# 140716_AriloTX_REV3_0_0_868MHZ_td.net
KiCad netlist of a schematic drawn in EAGLE
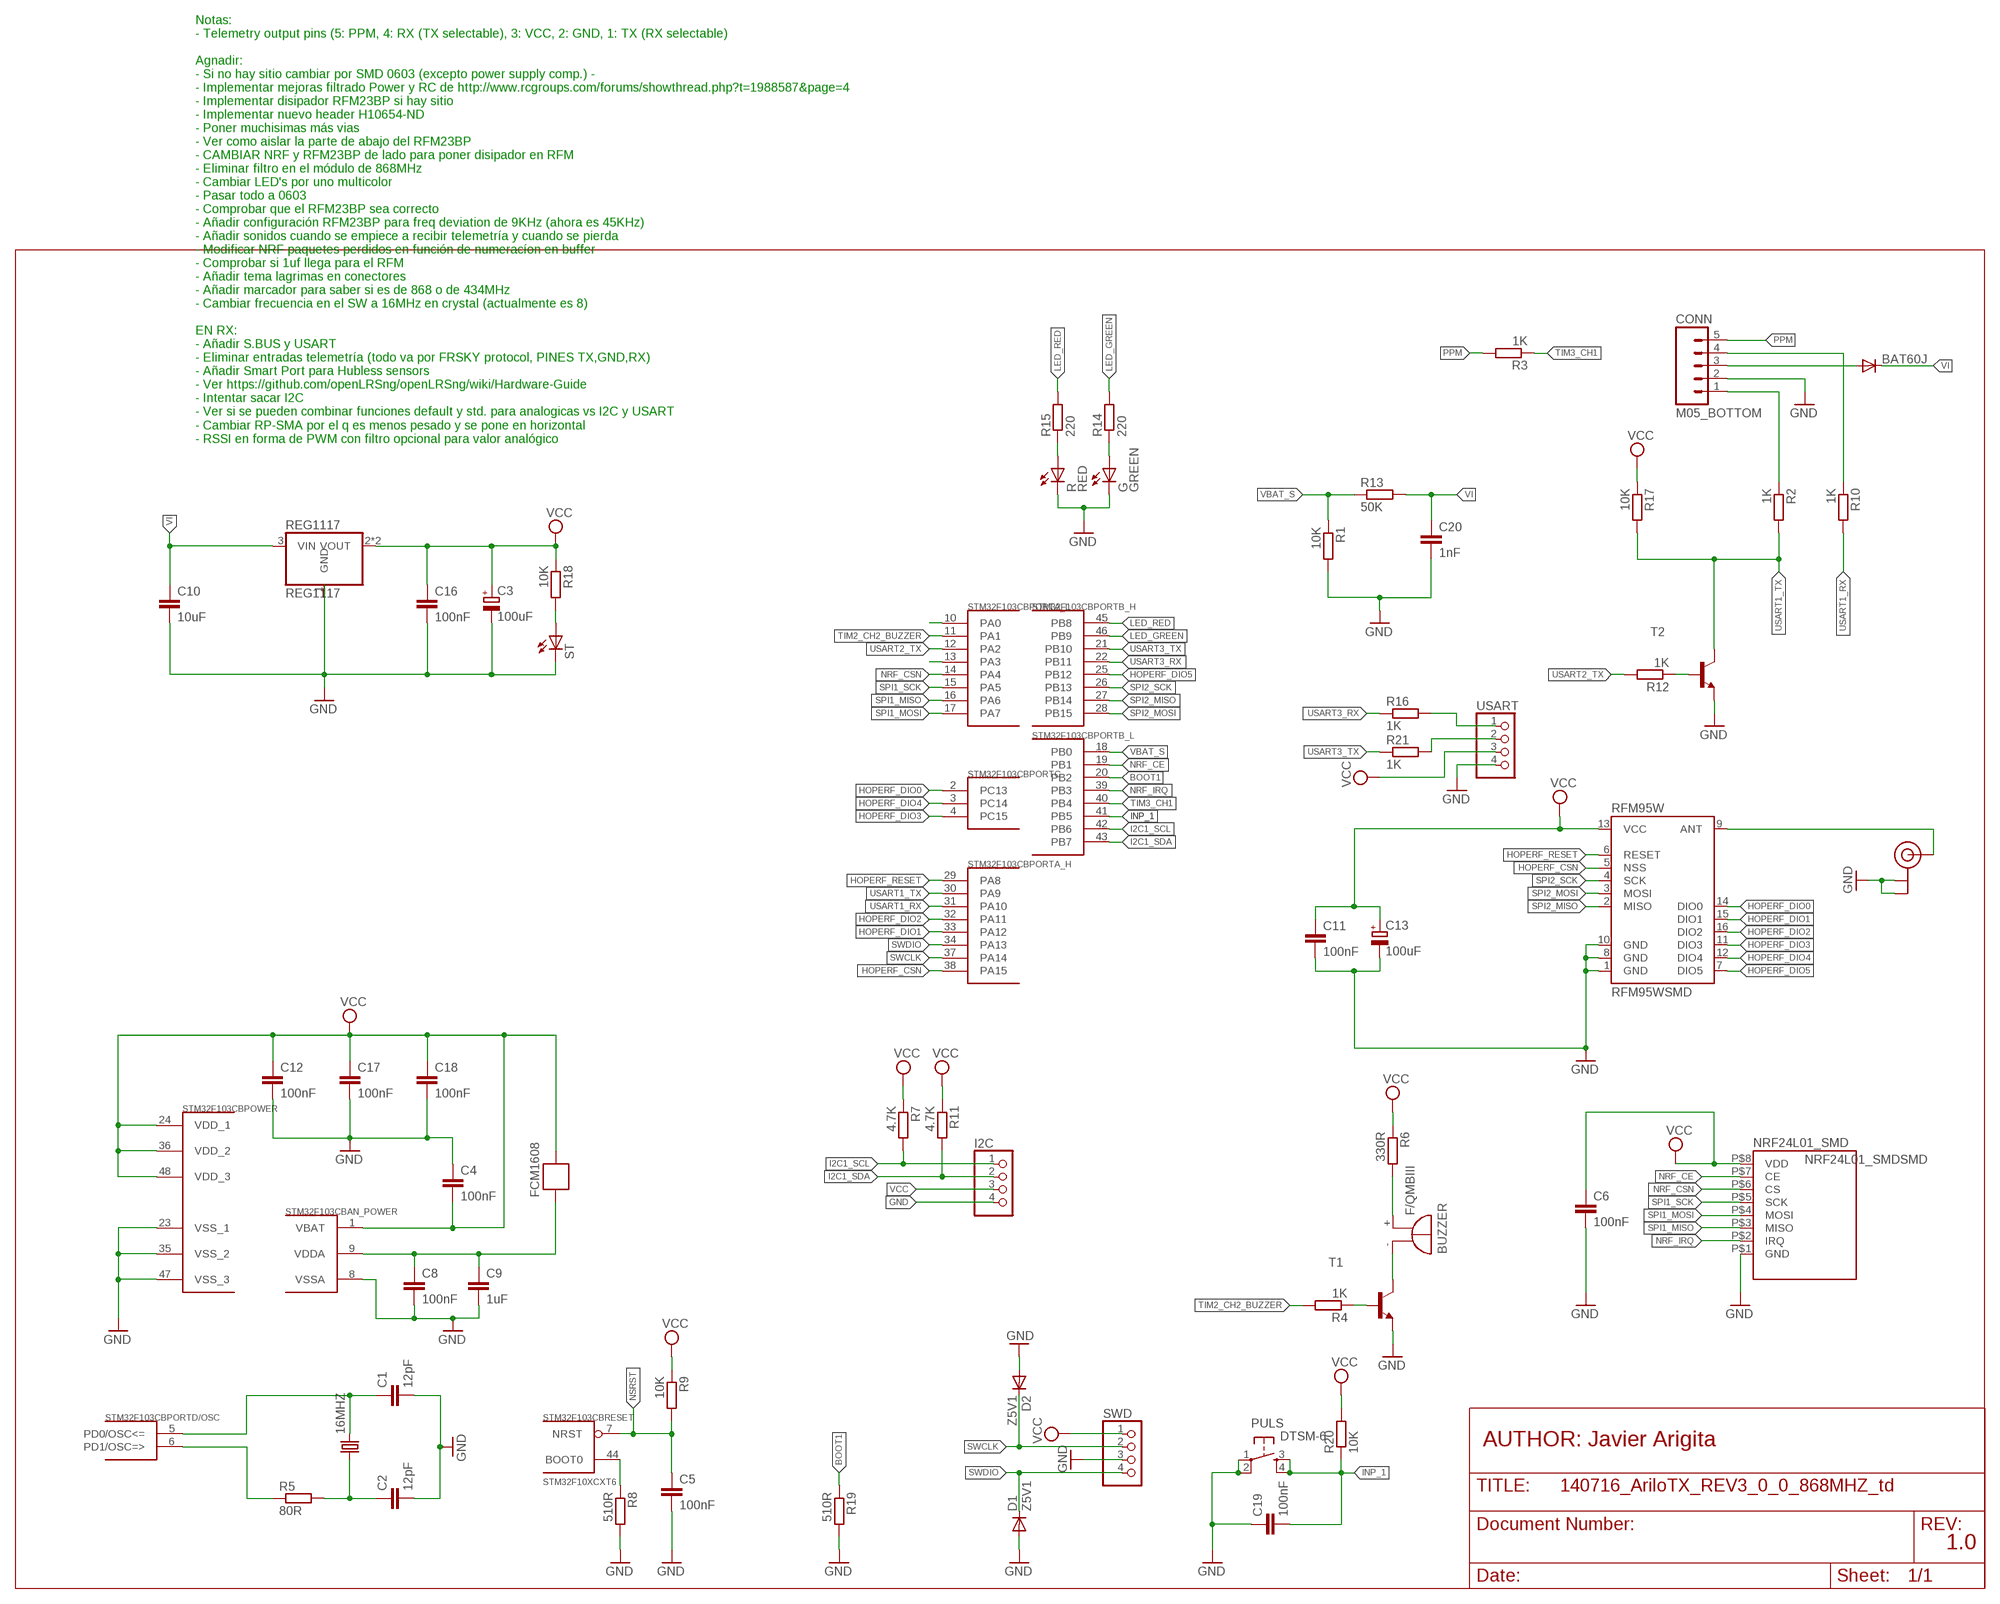
[diagram p0: schematic, sheet 1]

(export (version "E")
  (design (tool "Eeschema 10.0.6"))
  (components
    (comp (ref "16MHZ")
      (value "CRYSTAL5X3")
      (footprint "eagle-import:CRYSTAL-SMD-5X3")
      (libsource (lib "eagle-import") (part "CRYSTAL5X3"))
    )
    (comp (ref "BAT60J")
      (value "DIODE-SOD323-R")
      (footprint "eagle-import:SOD323-R")
      (libsource (lib "eagle-import") (part "DIODE-SOD323-R"))
    )
    (comp (ref "BUZZER")
      (value "F/QMBIII")
      (footprint "eagle-import:F_QMBIII")
      (libsource (lib "eagle-import") (part "F/QMBIII"))
    )
    (comp (ref "C1")
      (value "12pF")
      (footprint "eagle-import:C0603")
      (libsource (lib "eagle-import") (part "C-EUC0603"))
    )
    (comp (ref "C2")
      (value "12pF")
      (footprint "eagle-import:C0603")
      (libsource (lib "eagle-import") (part "C-EUC0603"))
    )
    (comp (ref "C3")
      (value "100uF")
      (footprint "eagle-import:SMC_B")
      (libsource (lib "eagle-import") (part "CPOL-EUSMCB"))
    )
    (comp (ref "C4")
      (value "100nF")
      (footprint "eagle-import:C0603")
      (libsource (lib "eagle-import") (part "C-EUC0603"))
    )
    (comp (ref "C5")
      (value "100nF")
      (footprint "eagle-import:C0603")
      (libsource (lib "eagle-import") (part "C-EUC0603"))
    )
    (comp (ref "C6")
      (value "100nF")
      (footprint "eagle-import:C0603")
      (libsource (lib "eagle-import") (part "C-EUC0603"))
    )
    (comp (ref "C8")
      (value "100nF")
      (footprint "eagle-import:C0603")
      (libsource (lib "eagle-import") (part "C-EUC0603"))
    )
    (comp (ref "C9")
      (value "1uF")
      (footprint "eagle-import:C0603")
      (libsource (lib "eagle-import") (part "C-EUC0603"))
    )
    (comp (ref "C10")
      (value "10uF")
      (footprint "eagle-import:C3216")
      (libsource (lib "eagle-import") (part "resistor_C-EUC3216"))
    )
    (comp (ref "C11")
      (value "100nF")
      (footprint "eagle-import:C0603")
      (libsource (lib "eagle-import") (part "C-EUC0603"))
    )
    (comp (ref "C12")
      (value "100nF")
      (footprint "eagle-import:C0603")
      (libsource (lib "eagle-import") (part "C-EUC0603"))
    )
    (comp (ref "C13")
      (value "100uF")
      (footprint "eagle-import:SMC_B")
      (libsource (lib "eagle-import") (part "CPOL-EUSMCB"))
    )
    (comp (ref "C16")
      (value "100nF")
      (footprint "eagle-import:C0603")
      (libsource (lib "eagle-import") (part "C-EUC0603"))
    )
    (comp (ref "C17")
      (value "100nF")
      (footprint "eagle-import:C0603")
      (libsource (lib "eagle-import") (part "C-EUC0603"))
    )
    (comp (ref "C18")
      (value "100nF")
      (footprint "eagle-import:C0603")
      (libsource (lib "eagle-import") (part "C-EUC0603"))
    )
    (comp (ref "C19")
      (value "100nF")
      (footprint "eagle-import:C0603")
      (libsource (lib "eagle-import") (part "C-EUC0603"))
    )
    (comp (ref "C20")
      (value "1nF")
      (footprint "eagle-import:C0603")
      (libsource (lib "eagle-import") (part "C-EUC0603"))
    )
    (comp (ref "CONN")
      (value "M05_BOTTOM")
      (footprint "eagle-import:M05_BOTTOM")
      (libsource (lib "eagle-import") (part "M05_BOTTOM"))
    )
    (comp (ref "D1")
      (value "Z5V1")
      (footprint "eagle-import:SOD323-R")
      (libsource (lib "eagle-import") (part "DIODE-SOD323-R"))
    )
    (comp (ref "D2")
      (value "Z5V1")
      (footprint "eagle-import:SOD323-R")
      (libsource (lib "eagle-import") (part "DIODE-SOD323-R"))
    )
    (comp (ref "FCM1608")
      (value "FERRITE-BEAD")
      (footprint "eagle-import:R0603")
      (libsource (lib "eagle-import") (part "FERRITE-BEAD"))
    )
    (comp (ref "G")
      (value "GREEN")
      (footprint "eagle-import:CHIP-LED0603")
      (libsource (lib "eagle-import") (part "LEDCHIP-LED0603"))
    )
    (comp (ref "I2C")
      (value "PINHD-1X4")
      (footprint "eagle-import:1X04")
      (libsource (lib "eagle-import") (part "PINHD-1X4"))
    )
    (comp (ref "NRF24L01_SMD")
      (value "NRF24L01_SMDSMD")
      (footprint "eagle-import:NRF24L01_SMD")
      (libsource (lib "eagle-import") (part "NRF24L01_SMDSMD"))
    )
    (comp (ref "PULS")
      (value "DTSM-6")
      (footprint "eagle-import:DTSM-6")
      (libsource (lib "eagle-import") (part "DTSM-6"))
    )
    (comp (ref "R")
      (value "RED")
      (footprint "eagle-import:CHIP-LED0603")
      (libsource (lib "eagle-import") (part "LEDCHIP-LED0603"))
    )
    (comp (ref "R1")
      (value "10K")
      (footprint "eagle-import:R0603")
      (libsource (lib "eagle-import") (part "R-EU_R0603"))
    )
    (comp (ref "R2")
      (value "1K")
      (footprint "eagle-import:R0603")
      (libsource (lib "eagle-import") (part "R-EU_R0603"))
    )
    (comp (ref "R3")
      (value "1K")
      (footprint "eagle-import:R0603")
      (libsource (lib "eagle-import") (part "R-EU_R0603"))
    )
    (comp (ref "R4")
      (value "1K")
      (footprint "eagle-import:R0603")
      (libsource (lib "eagle-import") (part "R-EU_R0603"))
    )
    (comp (ref "R5")
      (value "80R")
      (footprint "eagle-import:R0603")
      (libsource (lib "eagle-import") (part "R-EU_R0603"))
    )
    (comp (ref "R6")
      (value "330R")
      (footprint "eagle-import:R0603")
      (libsource (lib "eagle-import") (part "R-EU_R0603"))
    )
    (comp (ref "R7")
      (value "4.7K")
      (footprint "eagle-import:R0603")
      (libsource (lib "eagle-import") (part "R-EU_R0603"))
    )
    (comp (ref "R8")
      (value "510R")
      (footprint "eagle-import:R0603")
      (libsource (lib "eagle-import") (part "R-EU_R0603"))
    )
    (comp (ref "R9")
      (value "10K")
      (footprint "eagle-import:R0603")
      (libsource (lib "eagle-import") (part "R-EU_R0603"))
    )
    (comp (ref "R10")
      (value "1K")
      (footprint "eagle-import:R0603")
      (libsource (lib "eagle-import") (part "R-EU_R0603"))
    )
    (comp (ref "R11")
      (value "4.7K")
      (footprint "eagle-import:R0603")
      (libsource (lib "eagle-import") (part "R-EU_R0603"))
    )
    (comp (ref "R12")
      (value "1K")
      (footprint "eagle-import:R0603")
      (libsource (lib "eagle-import") (part "R-EU_R0603"))
    )
    (comp (ref "R13")
      (value "50K")
      (footprint "eagle-import:R0603")
      (libsource (lib "eagle-import") (part "R-EU_R0603"))
    )
    (comp (ref "R14")
      (value "220")
      (footprint "eagle-import:R0603")
      (libsource (lib "eagle-import") (part "R-EU_R0603"))
    )
    (comp (ref "R15")
      (value "220")
      (footprint "eagle-import:R0603")
      (libsource (lib "eagle-import") (part "R-EU_R0603"))
    )
    (comp (ref "R16")
      (value "1K")
      (footprint "eagle-import:R0603")
      (libsource (lib "eagle-import") (part "R-EU_R0603"))
    )
    (comp (ref "R17")
      (value "10K")
      (footprint "eagle-import:R0603")
      (libsource (lib "eagle-import") (part "R-EU_R0603"))
    )
    (comp (ref "R18")
      (value "10K")
      (footprint "eagle-import:R0603")
      (libsource (lib "eagle-import") (part "R-EU_R0603"))
    )
    (comp (ref "R19")
      (value "510R")
      (footprint "eagle-import:R0603")
      (libsource (lib "eagle-import") (part "R-EU_R0603"))
    )
    (comp (ref "R20")
      (value "10K")
      (footprint "eagle-import:R0603")
      (libsource (lib "eagle-import") (part "R-EU_R0603"))
    )
    (comp (ref "R21")
      (value "1K")
      (footprint "eagle-import:R0603")
      (libsource (lib "eagle-import") (part "R-EU_R0603"))
    )
    (comp (ref "REG1117")
      (value "REG1117")
      (footprint "eagle-import:SOT223")
      (libsource (lib "eagle-import") (part "REG1117"))
    )
    (comp (ref "RFM95W")
      (value "RFM95WSMD")
      (footprint "eagle-import:MISIEK_RFM95W_SMD")
      (libsource (lib "eagle-import") (part "MISIEK_RFM95WSMD"))
    )
    (comp (ref "ST")
      (value "LEDCHIP-LED0603")
      (footprint "eagle-import:CHIP-LED0603")
      (libsource (lib "eagle-import") (part "LEDCHIP-LED0603"))
    )
    (comp (ref "STM32F103CB")
      (value "STM32F10XCXT6")
      (footprint "eagle-import:TQFP48")
      (libsource (lib "eagle-import") (part "STM32F10XCXT6"))
    )
    (comp (ref "SWD")
      (value "PINHD-1X4")
      (footprint "eagle-import:1X04")
      (libsource (lib "eagle-import") (part "PINHD-1X4"))
    )
    (comp (ref "T1")
      (value "BC848-NPN-SOT23-BEC")
      (footprint "eagle-import:SOT23-BEC")
      (libsource (lib "eagle-import") (part "-NPN-SOT23-BECBC848"))
    )
    (comp (ref "T2")
      (value "BC848-NPN-SOT23-BEC")
      (footprint "eagle-import:SOT23-BEC")
      (libsource (lib "eagle-import") (part "-NPN-SOT23-BECBC848"))
    )
    (comp (ref "U.FL")
      (value "U.FL")
      (footprint "eagle-import:U.FL")
      (libsource (lib "eagle-import") (part "U.FL"))
    )
    (comp (ref "USART")
      (value "PINHD-1X4")
      (footprint "eagle-import:1X04")
      (libsource (lib "eagle-import") (part "PINHD-1X4"))
    )
  )
  (nets
    (net (code "1") (name "BOOT1") (class "Default")
      (node (ref "R19") (pin "1") (pinfunction "1_1") (pintype "passive"))
      (node (ref "STM32F103CB") (pin "20") (pinfunction "PB2_20") (pintype "bidirectional"))
    )
    (net (code "2") (name "GND") (class "Default")
      (node (ref "C1") (pin "2") (pinfunction "2_2") (pintype "passive"))
      (node (ref "C10") (pin "2") (pinfunction "2_2") (pintype "passive"))
      (node (ref "C11") (pin "2") (pinfunction "2_2") (pintype "passive"))
      (node (ref "C12") (pin "2") (pinfunction "2_2") (pintype "passive"))
      (node (ref "C13") (pin "-") (pinfunction "-_-") (pintype "passive"))
      (node (ref "C16") (pin "2") (pinfunction "2_2") (pintype "passive"))
      (node (ref "C17") (pin "2") (pinfunction "2_2") (pintype "passive"))
      (node (ref "C18") (pin "2") (pinfunction "2_2") (pintype "passive"))
      (node (ref "C19") (pin "1") (pinfunction "1_1") (pintype "passive"))
      (node (ref "C2") (pin "2") (pinfunction "2_2") (pintype "passive"))
      (node (ref "C20") (pin "2") (pinfunction "2_2") (pintype "passive"))
      (node (ref "C3") (pin "-") (pinfunction "-_-") (pintype "passive"))
      (node (ref "C4") (pin "1") (pinfunction "1_1") (pintype "passive"))
      (node (ref "C5") (pin "2") (pinfunction "2_2") (pintype "passive"))
      (node (ref "C6") (pin "2") (pinfunction "2_2") (pintype "passive"))
      (node (ref "C8") (pin "2") (pinfunction "2_2") (pintype "passive"))
      (node (ref "C9") (pin "2") (pinfunction "2_2") (pintype "passive"))
      (node (ref "CONN") (pin "2") (pinfunction "2_2") (pintype "passive"))
      (node (ref "D1") (pin "A") (pinfunction "A_A") (pintype "passive"))
      (node (ref "D2") (pin "A") (pinfunction "A_A") (pintype "passive"))
      (node (ref "G") (pin "C") (pinfunction "C_C") (pintype "passive"))
      (node (ref "I2C") (pin "4") (pinfunction "4_4") (pintype "passive"))
      (node (ref "NRF24L01_SMD") (pin "P$1") (pinfunction "GND_P$1") (pintype "power_in"))
      (node (ref "PULS") (pin "1") (pinfunction "1_1") (pintype "passive"))
      (node (ref "PULS") (pin "2") (pinfunction "2_2") (pintype "passive"))
      (node (ref "R") (pin "C") (pinfunction "C_C") (pintype "passive"))
      (node (ref "R1") (pin "2") (pinfunction "2_2") (pintype "passive"))
      (node (ref "R19") (pin "2") (pinfunction "2_2") (pintype "passive"))
      (node (ref "R8") (pin "2") (pinfunction "2_2") (pintype "passive"))
      (node (ref "REG1117") (pin "1") (pinfunction "GND_1") (pintype "power_in"))
      (node (ref "RFM95W") (pin "1") (pinfunction "GND_1") (pintype "power_in"))
      (node (ref "RFM95W") (pin "10") (pinfunction "GND_10") (pintype "power_in"))
      (node (ref "RFM95W") (pin "8") (pinfunction "GND_8") (pintype "power_in"))
      (node (ref "ST") (pin "C") (pinfunction "C_C") (pintype "passive"))
      (node (ref "STM32F103CB") (pin "23") (pinfunction "VSS_1_23") (pintype "power_in"))
      (node (ref "STM32F103CB") (pin "35") (pinfunction "VSS_2_35") (pintype "power_in"))
      (node (ref "STM32F103CB") (pin "47") (pinfunction "VSS_3_47") (pintype "power_in"))
      (node (ref "STM32F103CB") (pin "8") (pinfunction "VSSA_8") (pintype "power_in"))
      (node (ref "SWD") (pin "3") (pinfunction "3_3") (pintype "passive"))
      (node (ref "T1") (pin "E") (pinfunction "E_E") (pintype "passive"))
      (node (ref "T2") (pin "E") (pinfunction "E_E") (pintype "passive"))
      (node (ref "U.FL") (pin "P$1") (pinfunction "GND_P$1") (pintype "bidirectional"))
      (node (ref "U.FL") (pin "P$2") (pinfunction "GND_P$2") (pintype "bidirectional"))
      (node (ref "USART") (pin "4") (pinfunction "4_4") (pintype "passive"))
    )
    (net (code "3") (name "HOPERF_CSN") (class "Default")
      (node (ref "RFM95W") (pin "5") (pinfunction "NSS_5") (pintype "input"))
      (node (ref "STM32F103CB") (pin "38") (pinfunction "PA15_38") (pintype "bidirectional"))
    )
    (net (code "4") (name "HOPERF_DIO0") (class "Default")
      (node (ref "RFM95W") (pin "14") (pinfunction "DIO0_14") (pintype "input"))
      (node (ref "STM32F103CB") (pin "2") (pinfunction "PC13_2") (pintype "bidirectional"))
    )
    (net (code "5") (name "HOPERF_DIO1") (class "Default")
      (node (ref "RFM95W") (pin "15") (pinfunction "DIO1_15") (pintype "input"))
      (node (ref "STM32F103CB") (pin "33") (pinfunction "PA12_33") (pintype "bidirectional"))
    )
    (net (code "6") (name "HOPERF_DIO2") (class "Default")
      (node (ref "RFM95W") (pin "16") (pinfunction "DIO2_16") (pintype "input"))
      (node (ref "STM32F103CB") (pin "32") (pinfunction "PA11_32") (pintype "bidirectional"))
    )
    (net (code "7") (name "HOPERF_DIO3") (class "Default")
      (node (ref "RFM95W") (pin "11") (pinfunction "DIO3_11") (pintype "bidirectional"))
      (node (ref "STM32F103CB") (pin "4") (pinfunction "PC15_4") (pintype "bidirectional"))
    )
    (net (code "8") (name "HOPERF_DIO4") (class "Default")
      (node (ref "RFM95W") (pin "12") (pinfunction "DIO4_12") (pintype "bidirectional"))
      (node (ref "STM32F103CB") (pin "3") (pinfunction "PC14_3") (pintype "bidirectional"))
    )
    (net (code "9") (name "HOPERF_DIO5") (class "Default")
      (node (ref "RFM95W") (pin "7") (pinfunction "DIO5_7") (pintype "bidirectional"))
      (node (ref "STM32F103CB") (pin "25") (pinfunction "PB12_25") (pintype "bidirectional"))
    )
    (net (code "10") (name "HOPERF_RESET") (class "Default")
      (node (ref "RFM95W") (pin "6") (pinfunction "RESET_6") (pintype "output"))
      (node (ref "STM32F103CB") (pin "29") (pinfunction "PA8_29") (pintype "bidirectional"))
    )
    (net (code "11") (name "I2C1_SCL") (class "Default")
      (node (ref "I2C") (pin "1") (pinfunction "1_1") (pintype "passive"))
      (node (ref "R7") (pin "2") (pinfunction "2_2") (pintype "passive"))
      (node (ref "STM32F103CB") (pin "42") (pinfunction "PB6_42") (pintype "bidirectional"))
    )
    (net (code "12") (name "I2C1_SDA") (class "Default")
      (node (ref "I2C") (pin "2") (pinfunction "2_2") (pintype "passive"))
      (node (ref "R11") (pin "2") (pinfunction "2_2") (pintype "passive"))
      (node (ref "STM32F103CB") (pin "43") (pinfunction "PB7_43") (pintype "bidirectional"))
    )
    (net (code "13") (name "INP_1") (class "Default")
      (node (ref "C19") (pin "2") (pinfunction "2_2") (pintype "passive"))
      (node (ref "PULS") (pin "3") (pinfunction "3_3") (pintype "passive"))
      (node (ref "PULS") (pin "4") (pinfunction "4_4") (pintype "passive"))
      (node (ref "R20") (pin "1") (pinfunction "1_1") (pintype "passive"))
      (node (ref "STM32F103CB") (pin "41") (pinfunction "PB5_41") (pintype "bidirectional"))
    )
    (net (code "14") (name "LED_GREEN") (class "Default")
      (node (ref "R14") (pin "2") (pinfunction "2_2") (pintype "passive"))
      (node (ref "STM32F103CB") (pin "46") (pinfunction "PB9_46") (pintype "bidirectional"))
    )
    (net (code "15") (name "LED_RED") (class "Default")
      (node (ref "R15") (pin "2") (pinfunction "2_2") (pintype "passive"))
      (node (ref "STM32F103CB") (pin "45") (pinfunction "PB8_45") (pintype "bidirectional"))
    )
    (net (code "16") (name "NRF_CE") (class "Default")
      (node (ref "NRF24L01_SMD") (pin "P$7") (pinfunction "CE_P$7") (pintype "input"))
      (node (ref "STM32F103CB") (pin "19") (pinfunction "PB1_19") (pintype "bidirectional"))
    )
    (net (code "17") (name "NRF_CSN") (class "Default")
      (node (ref "NRF24L01_SMD") (pin "P$6") (pinfunction "CS_P$6") (pintype "input"))
      (node (ref "STM32F103CB") (pin "14") (pinfunction "PA4_14") (pintype "bidirectional"))
    )
    (net (code "18") (name "NRF_IRQ") (class "Default")
      (node (ref "NRF24L01_SMD") (pin "P$2") (pinfunction "IRQ_P$2") (pintype "output"))
      (node (ref "STM32F103CB") (pin "39") (pinfunction "PB3_39") (pintype "bidirectional"))
    )
    (net (code "19") (name "NSRST") (class "Default")
      (node (ref "C5") (pin "1") (pinfunction "1_1") (pintype "passive"))
      (node (ref "R9") (pin "2") (pinfunction "2_2") (pintype "passive"))
      (node (ref "STM32F103CB") (pin "7") (pinfunction "NRST_7") (pintype "input"))
    )
    (net (code "20") (name "Net-(16MHZ-2)") (class "Default")
      (node (ref "16MHZ") (pin "3") (pinfunction "2_3") (pintype "passive"))
      (node (ref "C1") (pin "1") (pinfunction "1_1") (pintype "passive"))
      (node (ref "STM32F103CB") (pin "5") (pinfunction "PD0/OSC<=_5") (pintype "bidirectional"))
    )
    (net (code "21") (name "Net-(16MHZ-Pad1)") (class "Default")
      (node (ref "16MHZ") (pin "1") (pinfunction "1_1") (pintype "passive"))
      (node (ref "C2") (pin "1") (pinfunction "1_1") (pintype "passive"))
      (node (ref "R5") (pin "2") (pinfunction "2_2") (pintype "passive"))
    )
    (net (code "22") (name "Net-(BAT60J-PadA)") (class "Default")
      (node (ref "BAT60J") (pin "A") (pinfunction "A_A") (pintype "passive"))
      (node (ref "CONN") (pin "3") (pinfunction "3_3") (pintype "passive"))
    )
    (net (code "23") (name "Net-(BUZZER-+)") (class "Default")
      (node (ref "BUZZER") (pin "-") (pinfunction "+_-") (pintype "passive"))
      (node (ref "T1") (pin "C") (pinfunction "C_C") (pintype "passive"))
    )
    (net (code "24") (name "Net-(BUZZER--)") (class "Default")
      (node (ref "BUZZER") (pin "+") (pinfunction "-_+") (pintype "passive"))
      (node (ref "R6") (pin "2") (pinfunction "2_2") (pintype "passive"))
    )
    (net (code "25") (name "Net-(CONN-Pad1)") (class "Default")
      (node (ref "CONN") (pin "1") (pinfunction "1_1") (pintype "passive"))
      (node (ref "R2") (pin "1") (pinfunction "1_1") (pintype "passive"))
    )
    (net (code "26") (name "Net-(CONN-Pad4)") (class "Default")
      (node (ref "CONN") (pin "4") (pinfunction "4_4") (pintype "passive"))
      (node (ref "R10") (pin "1") (pinfunction "1_1") (pintype "passive"))
    )
    (net (code "27") (name "Net-(FCM1608-P$2)") (class "Default")
      (node (ref "C8") (pin "1") (pinfunction "1_1") (pintype "passive"))
      (node (ref "C9") (pin "1") (pinfunction "1_1") (pintype "passive"))
      (node (ref "FCM1608") (pin "2") (pinfunction "P$2_2") (pintype "bidirectional"))
      (node (ref "STM32F103CB") (pin "9") (pinfunction "VDDA_9") (pintype "power_in"))
    )
    (net (code "28") (name "Net-(G-PadA)") (class "Default")
      (node (ref "G") (pin "A") (pinfunction "A_A") (pintype "passive"))
      (node (ref "R14") (pin "1") (pinfunction "1_1") (pintype "passive"))
    )
    (net (code "29") (name "Net-(R-PadA)") (class "Default")
      (node (ref "R") (pin "A") (pinfunction "A_A") (pintype "passive"))
      (node (ref "R15") (pin "1") (pinfunction "1_1") (pintype "passive"))
    )
    (net (code "30") (name "Net-(R4-Pad1)") (class "Default")
      (node (ref "R4") (pin "1") (pinfunction "1_1") (pintype "passive"))
      (node (ref "T1") (pin "B") (pinfunction "B_B") (pintype "passive"))
    )
    (net (code "31") (name "Net-(R12-Pad1)") (class "Default")
      (node (ref "R12") (pin "1") (pinfunction "1_1") (pintype "passive"))
      (node (ref "T2") (pin "B") (pinfunction "B_B") (pintype "passive"))
    )
    (net (code "32") (name "Net-(R16-Pad2)") (class "Default")
      (node (ref "R16") (pin "2") (pinfunction "2_2") (pintype "passive"))
      (node (ref "USART") (pin "1") (pinfunction "1_1") (pintype "passive"))
    )
    (net (code "33") (name "Net-(R18-Pad2)") (class "Default")
      (node (ref "R18") (pin "2") (pinfunction "2_2") (pintype "passive"))
      (node (ref "ST") (pin "A") (pinfunction "A_A") (pintype "passive"))
    )
    (net (code "34") (name "Net-(R21-Pad2)") (class "Default")
      (node (ref "R21") (pin "2") (pinfunction "2_2") (pintype "passive"))
      (node (ref "USART") (pin "2") (pinfunction "2_2") (pintype "passive"))
    )
    (net (code "35") (name "Net-(RFM95W-ANT)") (class "Default")
      (node (ref "RFM95W") (pin "9") (pinfunction "ANT_9") (pintype "bidirectional"))
      (node (ref "U.FL") (pin "P$3") (pinfunction "SIGNAL_P$3") (pintype "bidirectional"))
    )
    (net (code "36") (name "Net-(STM32F103CBG-PD1{slash}OSC=>)") (class "Default")
      (node (ref "R5") (pin "1") (pinfunction "1_1") (pintype "passive"))
      (node (ref "STM32F103CB") (pin "6") (pinfunction "PD1/OSC=>_6") (pintype "bidirectional"))
    )
    (net (code "37") (name "Net-(STM32F103CBI-BOOT0)") (class "Default")
      (node (ref "R8") (pin "1") (pinfunction "1_1") (pintype "passive"))
      (node (ref "STM32F103CB") (pin "44") (pinfunction "BOOT0_44") (pintype "input"))
    )
    (net (code "38") (name "PPM") (class "Default")
      (node (ref "CONN") (pin "5") (pinfunction "5_5") (pintype "passive"))
      (node (ref "R3") (pin "2") (pinfunction "2_2") (pintype "passive"))
    )
    (net (code "39") (name "SPI1_MISO") (class "Default")
      (node (ref "NRF24L01_SMD") (pin "P$3") (pinfunction "MISO_P$3") (pintype "output"))
      (node (ref "STM32F103CB") (pin "16") (pinfunction "PA6_16") (pintype "bidirectional"))
    )
    (net (code "40") (name "SPI1_MOSI") (class "Default")
      (node (ref "NRF24L01_SMD") (pin "P$4") (pinfunction "MOSI_P$4") (pintype "input"))
      (node (ref "STM32F103CB") (pin "17") (pinfunction "PA7_17") (pintype "bidirectional"))
    )
    (net (code "41") (name "SPI1_SCK") (class "Default")
      (node (ref "NRF24L01_SMD") (pin "P$5") (pinfunction "SCK_P$5") (pintype "input"))
      (node (ref "STM32F103CB") (pin "15") (pinfunction "PA5_15") (pintype "bidirectional"))
    )
    (net (code "42") (name "SPI2_MISO") (class "Default")
      (node (ref "RFM95W") (pin "2") (pinfunction "MISO_2") (pintype "output"))
      (node (ref "STM32F103CB") (pin "27") (pinfunction "PB14_27") (pintype "bidirectional"))
    )
    (net (code "43") (name "SPI2_MOSI") (class "Default")
      (node (ref "RFM95W") (pin "3") (pinfunction "MOSI_3") (pintype "input"))
      (node (ref "STM32F103CB") (pin "28") (pinfunction "PB15_28") (pintype "bidirectional"))
    )
    (net (code "44") (name "SPI2_SCK") (class "Default")
      (node (ref "RFM95W") (pin "4") (pinfunction "SCK_4") (pintype "input"))
      (node (ref "STM32F103CB") (pin "26") (pinfunction "PB13_26") (pintype "bidirectional"))
    )
    (net (code "45") (name "SWCLK") (class "Default")
      (node (ref "D2") (pin "C") (pinfunction "C_C") (pintype "passive"))
      (node (ref "STM32F103CB") (pin "37") (pinfunction "PA14_37") (pintype "bidirectional"))
      (node (ref "SWD") (pin "2") (pinfunction "2_2") (pintype "passive"))
    )
    (net (code "46") (name "SWDIO") (class "Default")
      (node (ref "D1") (pin "C") (pinfunction "C_C") (pintype "passive"))
      (node (ref "STM32F103CB") (pin "34") (pinfunction "PA13_34") (pintype "bidirectional"))
      (node (ref "SWD") (pin "4") (pinfunction "4_4") (pintype "passive"))
    )
    (net (code "47") (name "TIM2_CH2_BUZZER") (class "Default")
      (node (ref "R4") (pin "2") (pinfunction "2_2") (pintype "passive"))
      (node (ref "STM32F103CB") (pin "11") (pinfunction "PA1_11") (pintype "bidirectional"))
    )
    (net (code "48") (name "TIM3_CH1") (class "Default")
      (node (ref "R3") (pin "1") (pinfunction "1_1") (pintype "passive"))
      (node (ref "STM32F103CB") (pin "40") (pinfunction "PB4_40") (pintype "bidirectional"))
    )
    (net (code "49") (name "USART1_RX") (class "Default")
      (node (ref "R10") (pin "2") (pinfunction "2_2") (pintype "passive"))
      (node (ref "STM32F103CB") (pin "31") (pinfunction "PA10_31") (pintype "bidirectional"))
    )
    (net (code "50") (name "USART1_TX") (class "Default")
      (node (ref "R17") (pin "2") (pinfunction "2_2") (pintype "passive"))
      (node (ref "R2") (pin "2") (pinfunction "2_2") (pintype "passive"))
      (node (ref "STM32F103CB") (pin "30") (pinfunction "PA9_30") (pintype "bidirectional"))
      (node (ref "T2") (pin "C") (pinfunction "C_C") (pintype "passive"))
    )
    (net (code "51") (name "USART2_TX") (class "Default")
      (node (ref "R12") (pin "2") (pinfunction "2_2") (pintype "passive"))
      (node (ref "STM32F103CB") (pin "12") (pinfunction "PA2_12") (pintype "bidirectional"))
    )
    (net (code "52") (name "USART3_RX") (class "Default")
      (node (ref "R16") (pin "1") (pinfunction "1_1") (pintype "passive"))
      (node (ref "STM32F103CB") (pin "22") (pinfunction "PB11_22") (pintype "bidirectional"))
    )
    (net (code "53") (name "USART3_TX") (class "Default")
      (node (ref "R21") (pin "1") (pinfunction "1_1") (pintype "passive"))
      (node (ref "STM32F103CB") (pin "21") (pinfunction "PB10_21") (pintype "bidirectional"))
    )
    (net (code "54") (name "VBAT_S") (class "Default")
      (node (ref "R1") (pin "1") (pinfunction "1_1") (pintype "passive"))
      (node (ref "R13") (pin "1") (pinfunction "1_1") (pintype "passive"))
      (node (ref "STM32F103CB") (pin "18") (pinfunction "PB0_18") (pintype "bidirectional"))
    )
    (net (code "55") (name "VCC") (class "Default")
      (node (ref "C11") (pin "1") (pinfunction "1_1") (pintype "passive"))
      (node (ref "C12") (pin "1") (pinfunction "1_1") (pintype "passive"))
      (node (ref "C13") (pin "+") (pinfunction "+_+") (pintype "passive"))
      (node (ref "C16") (pin "1") (pinfunction "1_1") (pintype "passive"))
      (node (ref "C17") (pin "1") (pinfunction "1_1") (pintype "passive"))
      (node (ref "C18") (pin "1") (pinfunction "1_1") (pintype "passive"))
      (node (ref "C3") (pin "+") (pinfunction "+_+") (pintype "passive"))
      (node (ref "C4") (pin "2") (pinfunction "2_2") (pintype "passive"))
      (node (ref "C6") (pin "1") (pinfunction "1_1") (pintype "passive"))
      (node (ref "FCM1608") (pin "1") (pinfunction "P$1_1") (pintype "bidirectional"))
      (node (ref "I2C") (pin "3") (pinfunction "3_3") (pintype "passive"))
      (node (ref "NRF24L01_SMD") (pin "P$8") (pinfunction "VDD_P$8") (pintype "bidirectional"))
      (node (ref "R11") (pin "1") (pinfunction "1_1") (pintype "passive"))
      (node (ref "R17") (pin "1") (pinfunction "1_1") (pintype "passive"))
      (node (ref "R18") (pin "1") (pinfunction "1_1") (pintype "passive"))
      (node (ref "R20") (pin "2") (pinfunction "2_2") (pintype "passive"))
      (node (ref "R6") (pin "1") (pinfunction "1_1") (pintype "passive"))
      (node (ref "R7") (pin "1") (pinfunction "1_1") (pintype "passive"))
      (node (ref "R9") (pin "1") (pinfunction "1_1") (pintype "passive"))
      (node (ref "REG1117") (pin "2") (pinfunction "VOUT_2") (pintype "power_in"))
      (node (ref "REG1117") (pin "4") (pinfunction "VOUT_4") (pintype "power_in"))
      (node (ref "RFM95W") (pin "13") (pinfunction "VCC_13") (pintype "bidirectional"))
      (node (ref "STM32F103CB") (pin "1") (pinfunction "VBAT_1") (pintype "power_in"))
      (node (ref "STM32F103CB") (pin "24") (pinfunction "VDD_1_24") (pintype "power_in"))
      (node (ref "STM32F103CB") (pin "36") (pinfunction "VDD_2_36") (pintype "power_in"))
      (node (ref "STM32F103CB") (pin "48") (pinfunction "VDD_3_48") (pintype "power_in"))
      (node (ref "SWD") (pin "1") (pinfunction "1_1") (pintype "passive"))
      (node (ref "USART") (pin "3") (pinfunction "3_3") (pintype "passive"))
    )
    (net (code "56") (name "VI") (class "Default")
      (node (ref "BAT60J") (pin "C") (pinfunction "C_C") (pintype "passive"))
      (node (ref "C10") (pin "1") (pinfunction "1_1") (pintype "passive"))
      (node (ref "C20") (pin "1") (pinfunction "1_1") (pintype "passive"))
      (node (ref "R13") (pin "2") (pinfunction "2_2") (pintype "passive"))
      (node (ref "REG1117") (pin "3") (pinfunction "VIN_3") (pintype "input"))
    )
    (net (code "57") (name "unconnected-(STM32F103CBC-PA0-Pad10)") (class "Default")
      (node (ref "STM32F103CB") (pin "10") (pinfunction "PA0_10") (pintype "bidirectional"))
    )
    (net (code "58") (name "unconnected-(STM32F103CBC-PA3-Pad13)") (class "Default")
      (node (ref "STM32F103CB") (pin "13") (pinfunction "PA3_13") (pintype "bidirectional"))
    )
  )
)
